# analog-daughter-as-built.net
KiCad netlist of a schematic drawn in EAGLE
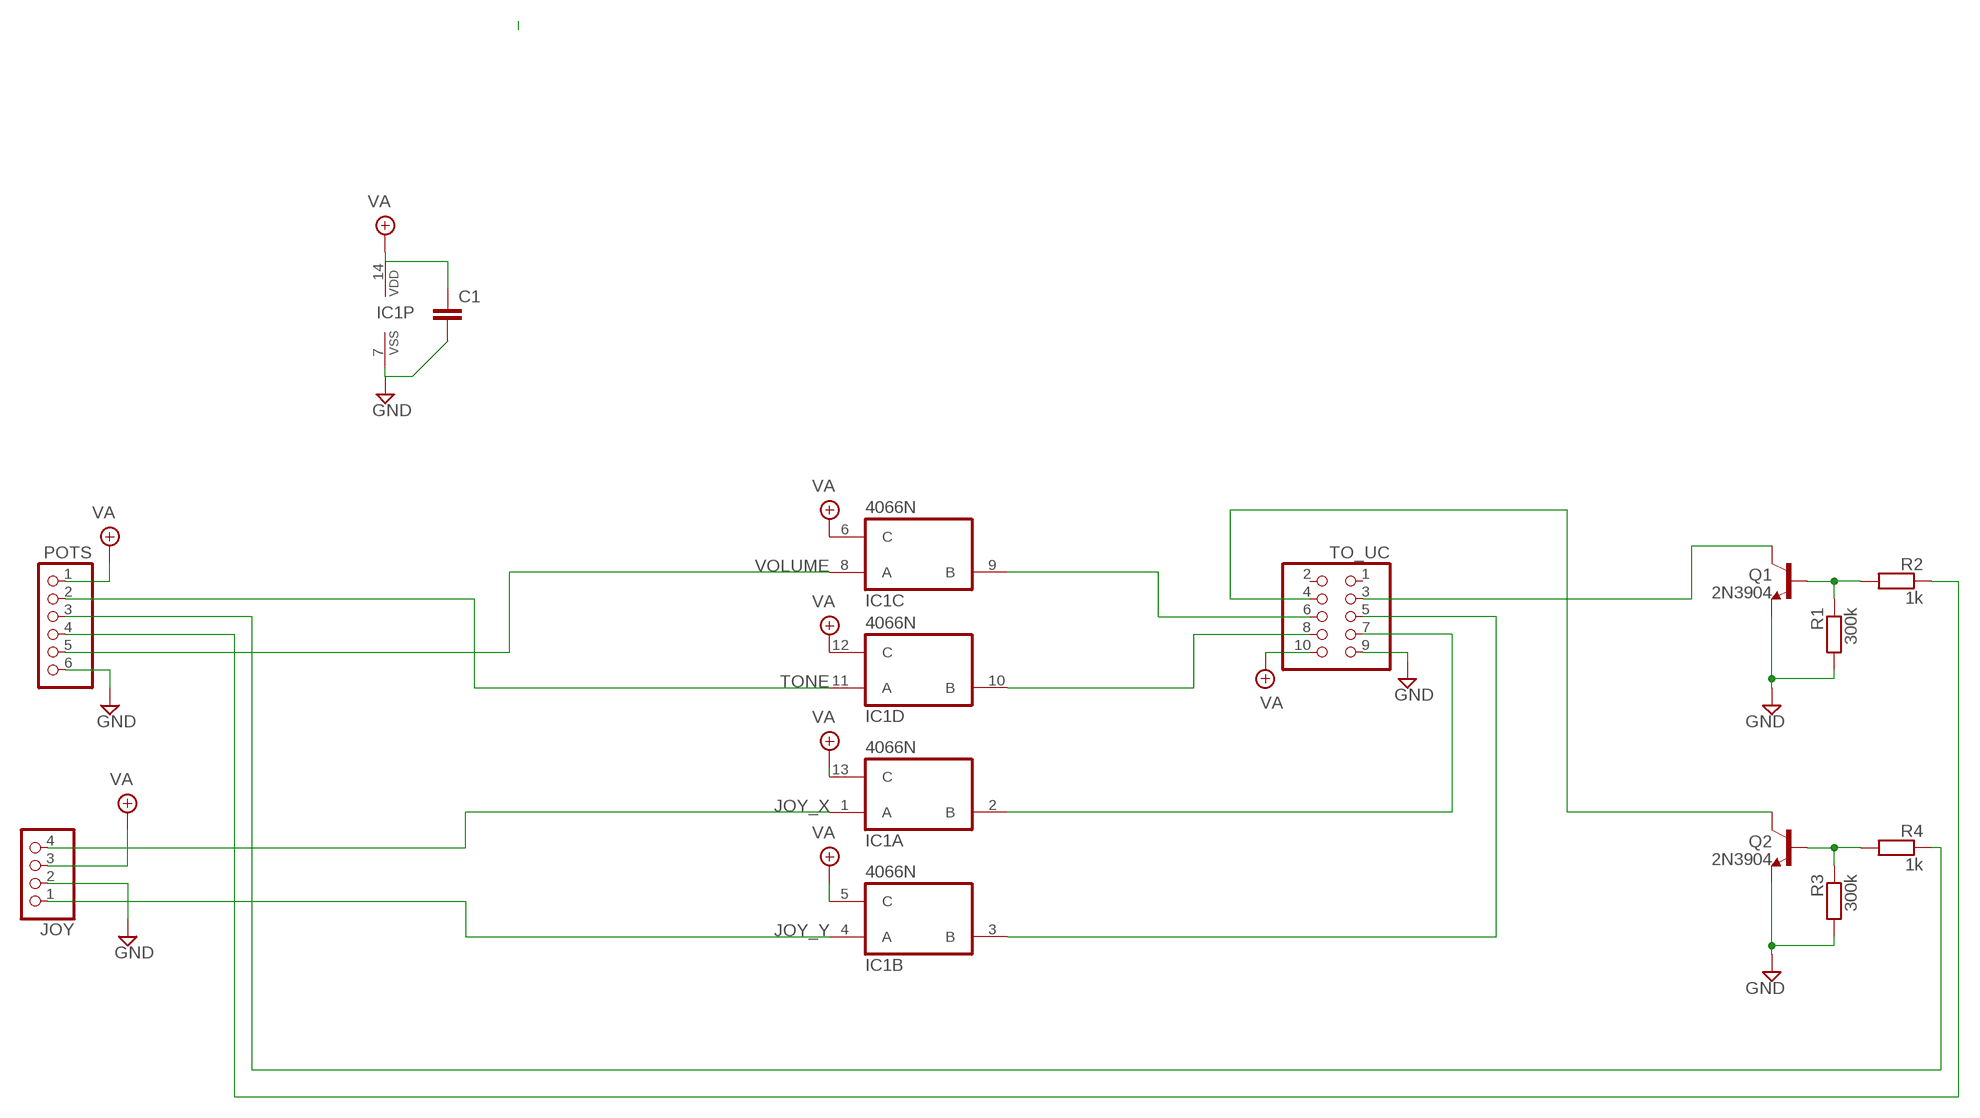
[diagram p0: schematic, sheet 1]

(export (version "E")
  (design (tool "Eeschema 10.0.6"))
  (components
    (comp (ref "C1")
      (value "050X030_0251")
      (footprint "eagle-import:050X030_025")
      (libsource (lib "eagle-import") (part "050X030_0251"))
    )
    (comp (ref "IC1")
      (value "4066N")
      (footprint "eagle-import:DIL14")
      (libsource (lib "eagle-import") (part "4066N"))
    )
    (comp (ref "JOY")
      (value "PINHD-1X4")
      (footprint "eagle-import:1X04")
      (libsource (lib "eagle-import") (part "PINHD-1X4"))
    )
    (comp (ref "POTS")
      (value "PINHD-1X6")
      (footprint "eagle-import:1X06")
      (libsource (lib "eagle-import") (part "PINHD-1X6"))
    )
    (comp (ref "Q1")
      (value "2N3904")
      (footprint "eagle-import:TO92-")
      (libsource (lib "eagle-import") (part "2N3904"))
    )
    (comp (ref "Q2")
      (value "2N3904")
      (footprint "eagle-import:TO92-")
      (libsource (lib "eagle-import") (part "2N3904"))
    )
    (comp (ref "R1")
      (value "300k")
      (footprint "eagle-import:R0207_3")
      (libsource (lib "eagle-import") (part "6MM-EU"))
    )
    (comp (ref "R2")
      (value "1k")
      (footprint "eagle-import:R0207_3")
      (libsource (lib "eagle-import") (part "6MM-EU"))
    )
    (comp (ref "R3")
      (value "300k")
      (footprint "eagle-import:R0207_3")
      (libsource (lib "eagle-import") (part "6MM-EU"))
    )
    (comp (ref "R4")
      (value "1k")
      (footprint "eagle-import:R0207_3")
      (libsource (lib "eagle-import") (part "6MM-EU"))
    )
    (comp (ref "TO_UC")
      (value "PINHD-2X5IDC")
      (footprint "eagle-import:10PIN_IDC")
      (libsource (lib "eagle-import") (part "PINHD-2X5IDC"))
    )
  )
  (nets
    (net (code "1") (name "/JOY_X") (class "Default")
      (node (ref "IC1") (pin "1") (pinfunction "A_1") (pintype "tri_state"))
      (node (ref "JOY") (pin "4") (pinfunction "4_4") (pintype "passive"))
    )
    (net (code "2") (name "/JOY_Y") (class "Default")
      (node (ref "IC1") (pin "4") (pinfunction "A_4") (pintype "tri_state"))
      (node (ref "JOY") (pin "1") (pinfunction "1_1") (pintype "passive"))
    )
    (net (code "3") (name "/TONE") (class "Default")
      (node (ref "IC1") (pin "11") (pinfunction "A_11") (pintype "tri_state"))
      (node (ref "POTS") (pin "2") (pinfunction "2_2") (pintype "passive"))
    )
    (net (code "4") (name "/VOLUME") (class "Default")
      (node (ref "IC1") (pin "8") (pinfunction "A_8") (pintype "tri_state"))
      (node (ref "POTS") (pin "5") (pinfunction "5_5") (pintype "passive"))
    )
    (net (code "5") (name "GND") (class "Default")
      (node (ref "C1") (pin "2") (pinfunction "2_2") (pintype "passive"))
      (node (ref "IC1") (pin "7") (pinfunction "VSS_7") (pintype "power_in"))
      (node (ref "JOY") (pin "2") (pinfunction "2_2") (pintype "passive"))
      (node (ref "POTS") (pin "6") (pinfunction "6_6") (pintype "passive"))
      (node (ref "Q1") (pin "3") (pinfunction "E_3") (pintype "passive"))
      (node (ref "Q2") (pin "3") (pinfunction "E_3") (pintype "passive"))
      (node (ref "R1") (pin "2") (pinfunction "2_2") (pintype "passive"))
      (node (ref "R3") (pin "2") (pinfunction "2_2") (pintype "passive"))
      (node (ref "TO_UC") (pin "9") (pinfunction "9_9") (pintype "passive"))
    )
    (net (code "6") (name "Net-(IC1A-B)") (class "Default")
      (node (ref "IC1") (pin "2") (pinfunction "B_2") (pintype "tri_state"))
      (node (ref "TO_UC") (pin "7") (pinfunction "7_7") (pintype "passive"))
    )
    (net (code "7") (name "Net-(IC1B-B)") (class "Default")
      (node (ref "IC1") (pin "3") (pinfunction "B_3") (pintype "tri_state"))
      (node (ref "TO_UC") (pin "5") (pinfunction "5_5") (pintype "passive"))
    )
    (net (code "8") (name "Net-(IC1C-B)") (class "Default")
      (node (ref "IC1") (pin "9") (pinfunction "B_9") (pintype "tri_state"))
      (node (ref "TO_UC") (pin "6") (pinfunction "6_6") (pintype "passive"))
    )
    (net (code "9") (name "Net-(IC1D-B)") (class "Default")
      (node (ref "IC1") (pin "10") (pinfunction "B_10") (pintype "tri_state"))
      (node (ref "TO_UC") (pin "8") (pinfunction "8_8") (pintype "passive"))
    )
    (net (code "10") (name "Net-(POTS-Pad3)") (class "Default")
      (node (ref "POTS") (pin "3") (pinfunction "3_3") (pintype "passive"))
      (node (ref "R4") (pin "1") (pinfunction "1_1") (pintype "passive"))
    )
    (net (code "11") (name "Net-(POTS-Pad4)") (class "Default")
      (node (ref "POTS") (pin "4") (pinfunction "4_4") (pintype "passive"))
      (node (ref "R2") (pin "1") (pinfunction "1_1") (pintype "passive"))
    )
    (net (code "12") (name "Net-(Q1-B)") (class "Default")
      (node (ref "Q1") (pin "2") (pinfunction "B_2") (pintype "passive"))
      (node (ref "R1") (pin "1") (pinfunction "1_1") (pintype "passive"))
      (node (ref "R2") (pin "2") (pinfunction "2_2") (pintype "passive"))
    )
    (net (code "13") (name "Net-(Q1-C)") (class "Default")
      (node (ref "Q1") (pin "1") (pinfunction "C_1") (pintype "passive"))
      (node (ref "TO_UC") (pin "3") (pinfunction "3_3") (pintype "passive"))
    )
    (net (code "14") (name "Net-(Q2-B)") (class "Default")
      (node (ref "Q2") (pin "2") (pinfunction "B_2") (pintype "passive"))
      (node (ref "R3") (pin "1") (pinfunction "1_1") (pintype "passive"))
      (node (ref "R4") (pin "2") (pinfunction "2_2") (pintype "passive"))
    )
    (net (code "15") (name "Net-(Q2-C)") (class "Default")
      (node (ref "Q2") (pin "1") (pinfunction "C_1") (pintype "passive"))
      (node (ref "TO_UC") (pin "4") (pinfunction "4_4") (pintype "passive"))
    )
    (net (code "16") (name "VA") (class "Default")
      (node (ref "C1") (pin "1") (pinfunction "1_1") (pintype "passive"))
      (node (ref "IC1") (pin "12") (pinfunction "C_12") (pintype "input"))
      (node (ref "IC1") (pin "13") (pinfunction "C_13") (pintype "input"))
      (node (ref "IC1") (pin "14") (pinfunction "VDD_14") (pintype "power_in"))
      (node (ref "IC1") (pin "5") (pinfunction "C_5") (pintype "input"))
      (node (ref "IC1") (pin "6") (pinfunction "C_6") (pintype "input"))
      (node (ref "JOY") (pin "3") (pinfunction "3_3") (pintype "passive"))
      (node (ref "POTS") (pin "1") (pinfunction "1_1") (pintype "passive"))
      (node (ref "TO_UC") (pin "10") (pinfunction "10_10") (pintype "passive"))
    )
    (net (code "17") (name "unconnected-(TO_UC-Pad1)") (class "Default")
      (node (ref "TO_UC") (pin "1") (pinfunction "1_1") (pintype "passive"))
    )
    (net (code "18") (name "unconnected-(TO_UC-Pad2)") (class "Default")
      (node (ref "TO_UC") (pin "2") (pinfunction "2_2") (pintype "passive"))
    )
  )
)
